# CAN_PHY.net
KiCad netlist of a schematic drawn in Altium Designer
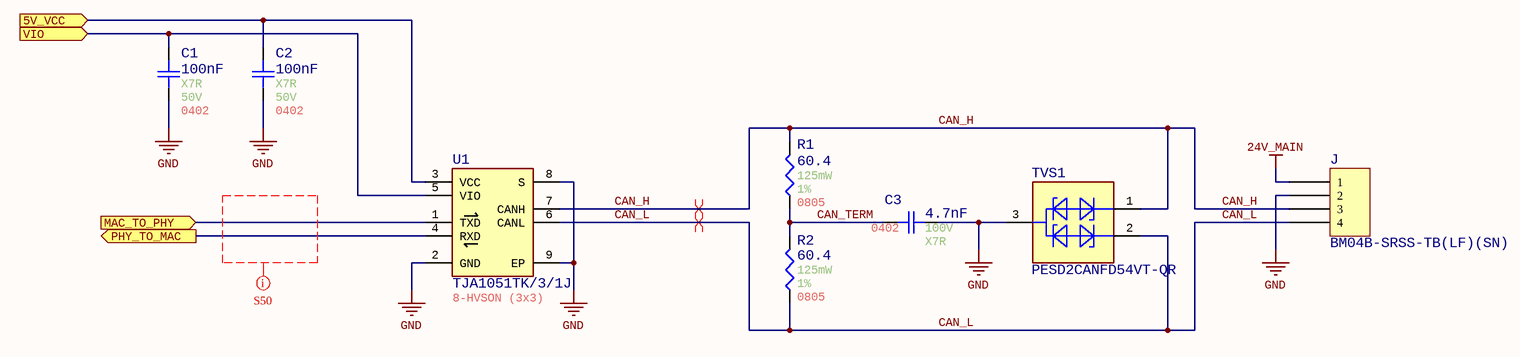
[diagram p0: CAN_PHY.SchDoc]

(export (version "E")
  (design (tool "Eeschema 10.0.6"))
  (components
    (comp (ref "C1")
      (value "100nF")
      (footprint "Generic 0402 capacitor")
      (fields
        (field (name "TEMPERATURE COEFFICIENT") "X7R")
        (field (name "VOLTAGE RATING") "50V")
        (field (name "CASE/PACKAGE") "0402")
        (field (name "TOLERANCE") "10%")
        (field (name "Comment") "GRT155R71H104KE01D")
      )
      (libsource (lib "Raise Robotics") (part "Unpolarized Capacitor"))
    )
    (comp (ref "C2")
      (value "100nF")
      (footprint "Generic 0402 capacitor")
      (fields
        (field (name "TEMPERATURE COEFFICIENT") "X7R")
        (field (name "VOLTAGE RATING") "50V")
        (field (name "CASE/PACKAGE") "0402")
        (field (name "TOLERANCE") "10%")
        (field (name "Comment") "GRT155R71H104KE01D")
      )
      (libsource (lib "Raise Robotics") (part "Unpolarized Capacitor"))
    )
    (comp (ref "C3")
      (value "4.7nF")
      (footprint "Generic 0402 capacitor")
      (fields
        (field (name "TEMPERATURE COEFFICIENT") "X7R")
        (field (name "VOLTAGE RATING") "100V")
        (field (name "CASE/PACKAGE") "0402")
        (field (name "TOLERANCE") "10%")
        (field (name "Comment") "GCM155R72A472KA37D")
      )
      (libsource (lib "Raise Robotics") (part "Unpolarized Capacitor"))
    )
    (comp (ref "J")
      (value "BM04B-SRSS-TB(LF)(SN)")
      (footprint "JST BM04B-SRSS-TB")
      (description "CONN HEADER SMD 4POS 1MM")
      (fields (field (name "MANUFACTURER") "JST Sales America Inc."))
      (libsource (lib "Celestial Altium Library - altium_library") (part "4 Pin"))
    )
    (comp (ref "R1")
      (value "60.4")
      (footprint "0805 Resistor")
      (description "Res 60.4 Ohm 1% 1/8W 0805")
      (fields
        (field (name "POWER") "125mW")
        (field (name "TOLERANCE") "1%")
        (field (name "CASE/PACKAGE") "0805")
        (field (name "MANUFACTURER PART NUMBER") "TFA0805R60R4F-T5")
      )
      (libsource (lib "Raise Robotics") (part "Resistor"))
    )
    (comp (ref "R2")
      (value "60.4")
      (footprint "0805 Resistor")
      (description "Res 60.4 Ohm 1% 1/8W 0805")
      (fields
        (field (name "POWER") "125mW")
        (field (name "TOLERANCE") "1%")
        (field (name "CASE/PACKAGE") "0805")
        (field (name "MANUFACTURER PART NUMBER") "TFA0805R60R4F-T5")
      )
      (libsource (lib "Raise Robotics") (part "Resistor"))
    )
    (comp (ref "TVS1")
      (value "PESD2CANFD54VT-QR")
      (footprint "PESD2CANFD54VT-QR")
      (description "ESD protection for in-vehicle networks")
      (libsource (lib "Raise Robotics") (part "PESD2CANFD54VT-QRVS"))
    )
    (comp (ref "U1")
      (value "TJA1051TK/3/1J")
      (footprint "TJA1044xxK")
      (description "Interface Circuit, PDSO8")
      (fields (field (name "CASE/PACKAGE") "8-HVSON (3x3)"))
      (libsource (lib "Raise Robotics") (part "TJA1044"))
    )
  )
  (nets
    (net (code "1") (name "/5V_VCC") (class "Default")
      (node (ref "C2") (pin "1") (pinfunction "1_1") (pintype "passive"))
      (node (ref "U1") (pin "3") (pinfunction "VCC_3") (pintype "passive"))
    )
    (net (code "2") (name "/CAN_H") (class "Default")
      (node (ref "J") (pin "3") (pinfunction "3_3") (pintype "passive"))
      (node (ref "R1") (pin "2") (pinfunction "2_2") (pintype "passive"))
      (node (ref "TVS1") (pin "1") (pinfunction "K1_1") (pintype "passive"))
      (node (ref "U1") (pin "7") (pinfunction "CANH_7") (pintype "passive"))
    )
    (net (code "3") (name "/CAN_L") (class "Default")
      (node (ref "J") (pin "4") (pinfunction "4_4") (pintype "passive"))
      (node (ref "R2") (pin "1") (pinfunction "1_1") (pintype "passive"))
      (node (ref "TVS1") (pin "2") (pinfunction "K2_2") (pintype "passive"))
      (node (ref "U1") (pin "6") (pinfunction "CANL_6") (pintype "passive"))
    )
    (net (code "4") (name "/CAN_TERM") (class "Default")
      (node (ref "C3") (pin "2") (pinfunction "2_2") (pintype "passive"))
      (node (ref "R1") (pin "1") (pinfunction "1_1") (pintype "passive"))
      (node (ref "R2") (pin "2") (pinfunction "2_2") (pintype "passive"))
    )
    (net (code "5") (name "/MAC_TO_PHY") (class "Default")
      (node (ref "U1") (pin "1") (pinfunction "TXD_1") (pintype "passive"))
    )
    (net (code "6") (name "/PHY_TO_MAC") (class "Default")
      (node (ref "U1") (pin "4") (pinfunction "RXD_4") (pintype "passive"))
    )
    (net (code "7") (name "/VIO") (class "Default")
      (node (ref "C1") (pin "1") (pinfunction "1_1") (pintype "passive"))
      (node (ref "U1") (pin "5") (pinfunction "VIO_5") (pintype "passive"))
    )
    (net (code "8") (name "24V_MAIN") (class "Default")
      (node (ref "J") (pin "1") (pinfunction "1_1") (pintype "passive"))
    )
    (net (code "9") (name "GND") (class "Default")
      (node (ref "C1") (pin "2") (pinfunction "2_2") (pintype "passive"))
      (node (ref "C2") (pin "2") (pinfunction "2_2") (pintype "passive"))
      (node (ref "C3") (pin "1") (pinfunction "1_1") (pintype "passive"))
      (node (ref "J") (pin "2") (pinfunction "2_2") (pintype "passive"))
      (node (ref "TVS1") (pin "3") (pinfunction "CC_3") (pintype "passive"))
      (node (ref "U1") (pin "2") (pinfunction "GND_2") (pintype "passive"))
      (node (ref "U1") (pin "8") (pinfunction "S_8") (pintype "passive"))
      (node (ref "U1") (pin "9") (pinfunction "EP_9") (pintype "passive"))
    )
  )
)
